# quadruped.net
KiCad netlist of a schematic drawn in Altium Designer
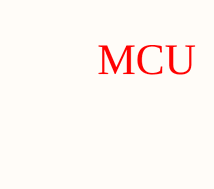
[diagram p0: quadruped.SchDoc, top left]
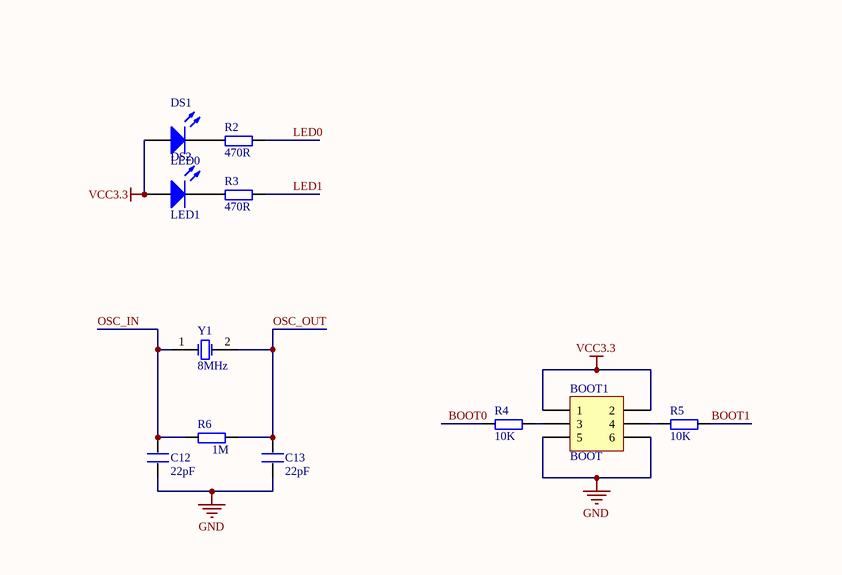
[diagram p1: quadruped.SchDoc, top right]
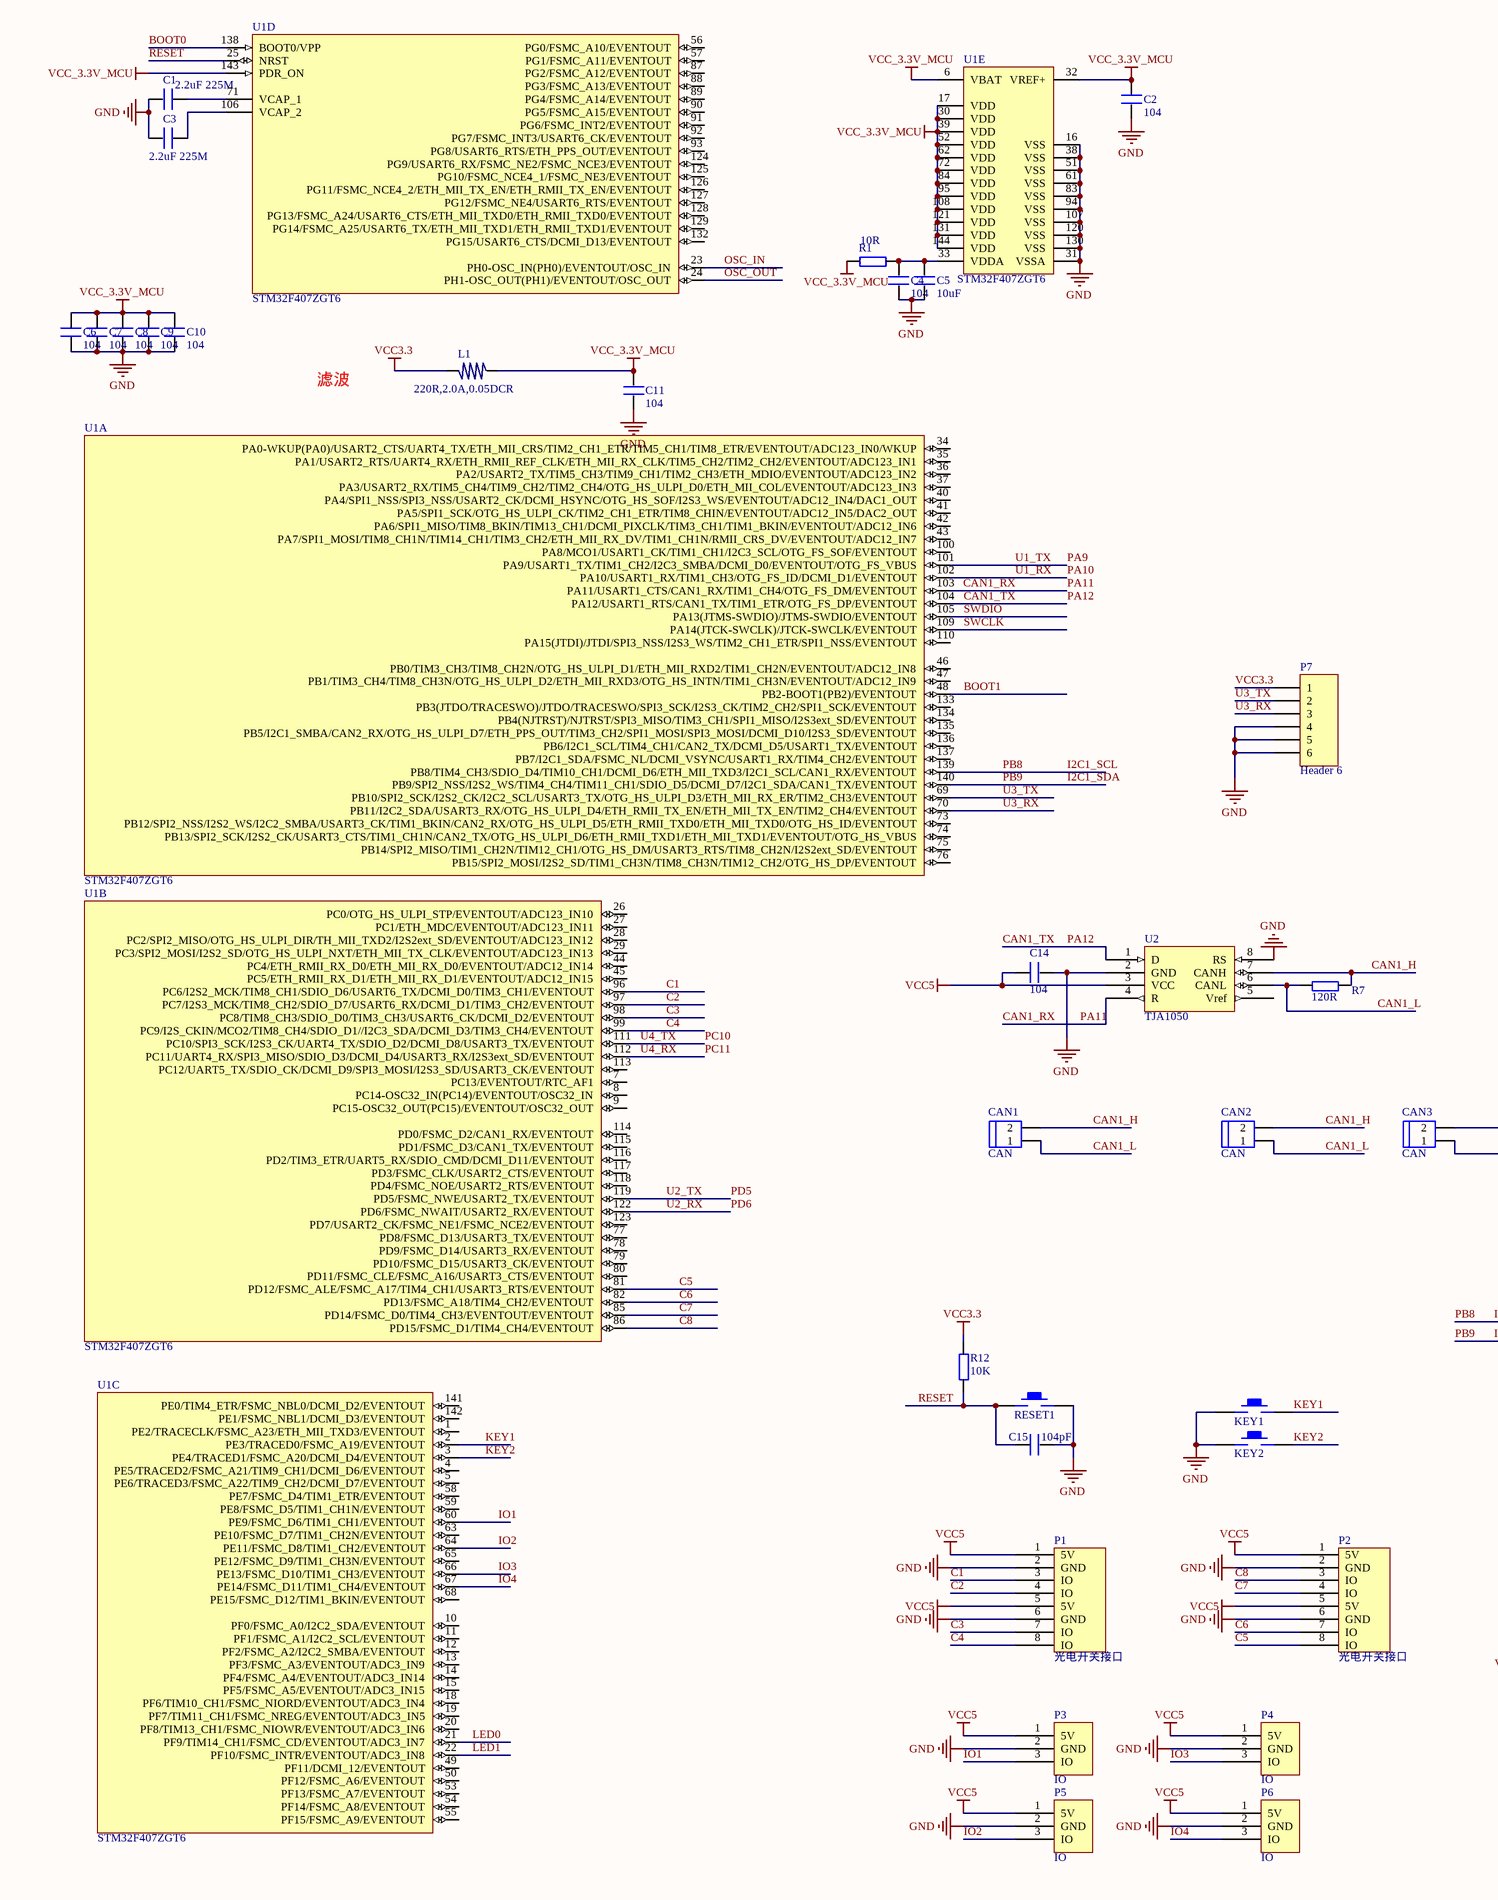
[diagram p2: quadruped.SchDoc, bottom left]
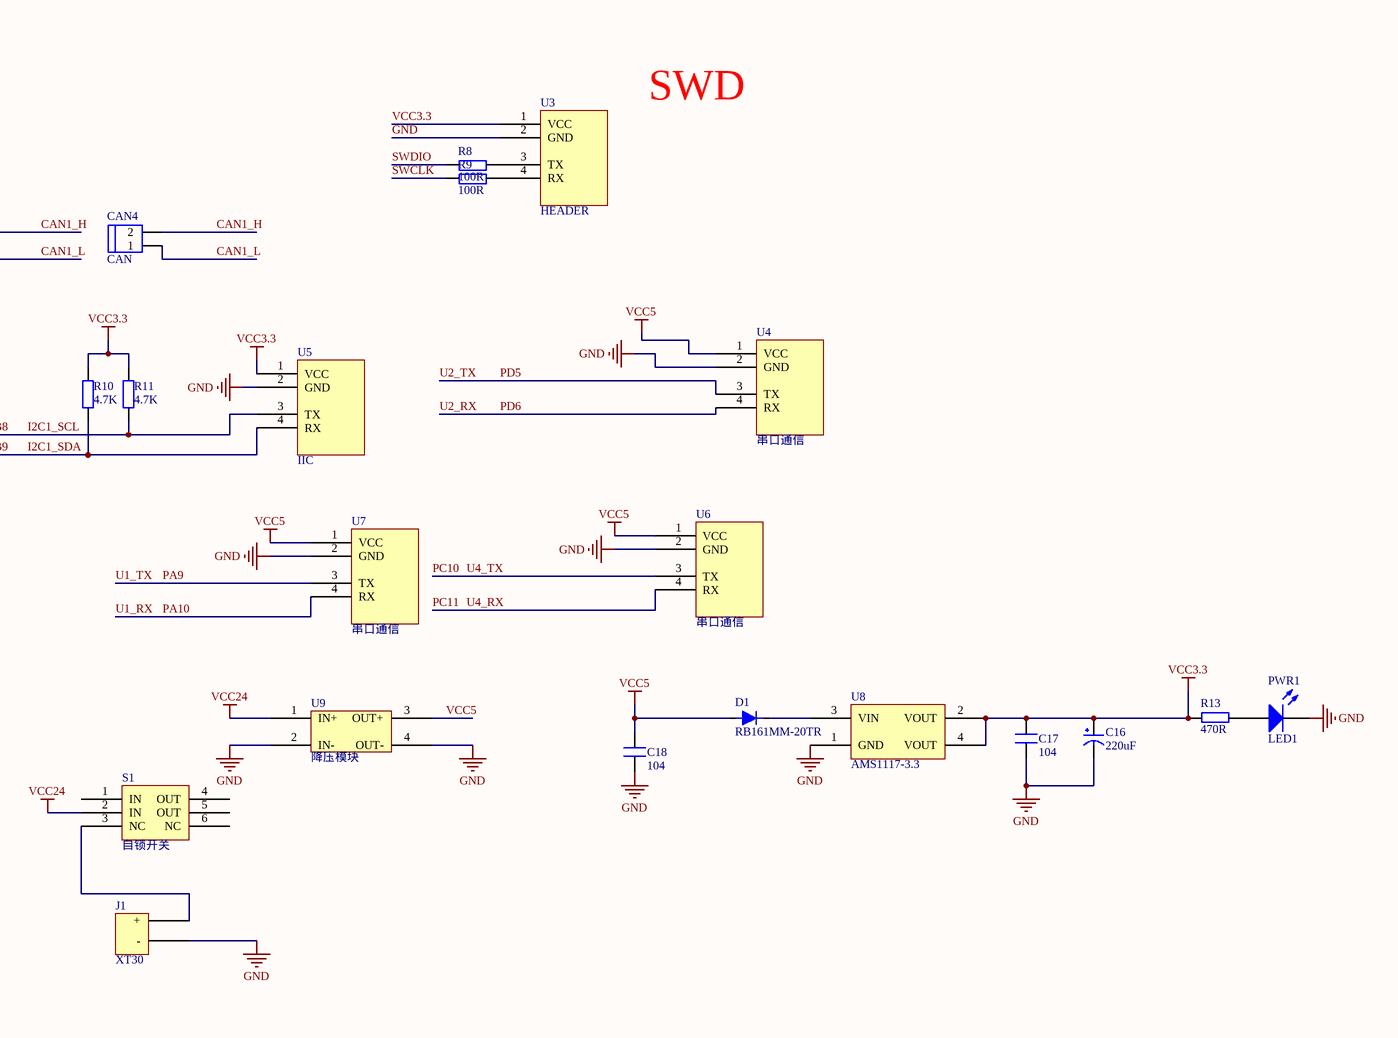
[diagram p3: quadruped.SchDoc, bottom right]

(export (version "E")
  (design (tool "Eeschema 10.0.6"))
  (components
    (comp (ref "BOOT1")
      (value "BOOT")
      (footprint "HDR2X3")
      (description "Header, 3-Pin, Dual row")
      (fields (field (name "PUBLISHER") "Altium Limited"))
      (libsource (lib "Explorer STM32F407封装库2") (part "Header 3X2"))
    )
    (comp (ref "C1")
      (value "2.2uF 225M")
      (footprint "0603C")
      (libsource (lib "Explorer STM32F407封装库") (part "C"))
    )
    (comp (ref "C2") (value "104") (footprint "0603C") (libsource (lib "Explorer STM32F407封装库") (part "C_1")))
    (comp (ref "C3")
      (value "2.2uF 225M")
      (footprint "0603C")
      (libsource (lib "Explorer STM32F407封装库") (part "C"))
    )
    (comp (ref "C4") (value "104") (footprint "0603C") (libsource (lib "Explorer STM32F407封装库") (part "C")))
    (comp (ref "C5") (value "10uF") (footprint "0603C") (libsource (lib "Explorer STM32F407封装库") (part "C")))
    (comp (ref "C6") (value "104") (footprint "0603C") (libsource (lib "Explorer STM32F407封装库") (part "C")))
    (comp (ref "C7") (value "104") (footprint "0603C") (libsource (lib "Explorer STM32F407封装库") (part "C")))
    (comp (ref "C8") (value "104") (footprint "0603C") (libsource (lib "Explorer STM32F407封装库") (part "C")))
    (comp (ref "C9") (value "104") (footprint "0603C") (libsource (lib "Explorer STM32F407封装库") (part "C")))
    (comp (ref "C10") (value "104") (footprint "0603C") (libsource (lib "Explorer STM32F407封装库") (part "C")))
    (comp (ref "C11") (value "104") (footprint "0603C") (libsource (lib "Explorer STM32F407封装库") (part "C")))
    (comp (ref "C12") (value "22pF") (footprint "0603C") (libsource (lib "Explorer STM32F407封装库") (part "C")))
    (comp (ref "C13") (value "22pF") (footprint "0603C") (libsource (lib "Explorer STM32F407封装库") (part "C")))
    (comp (ref "C14") (value "104") (footprint "0603C") (libsource (lib "Explorer STM32F407封装库") (part "C")))
    (comp (ref "C15")
      (value "104pF")
      (footprint "C0603")
      (libsource (lib "Explorer STM32F407封装库2") (part "C"))
    )
    (comp (ref "C16") (value "220uF") (footprint "C3528") (libsource (lib "EXPLORER") (part "CAP")))
    (comp (ref "C17")
      (value "104")
      (footprint "0603C")
      (libsource (lib "Explorer STM32F407封装库_SCH") (part "C"))
    )
    (comp (ref "C18")
      (value "104")
      (footprint "0603C")
      (libsource (lib "Explorer STM32F407封装库_SCH") (part "C"))
    )
    (comp (ref "CAN1")
      (value "CAN")
      (footprint "KF3.81直针-2P")
      (libsource (lib "Explorer STM32F407封装库") (part "HEAD2"))
    )
    (comp (ref "CAN2")
      (value "CAN")
      (footprint "KF3.81直针-2P")
      (libsource (lib "Explorer STM32F407封装库") (part "HEAD2"))
    )
    (comp (ref "CAN3")
      (value "CAN")
      (footprint "KF3.81直针-2P")
      (libsource (lib "Explorer STM32F407封装库") (part "HEAD2"))
    )
    (comp (ref "CAN4")
      (value "CAN")
      (footprint "KF3.81直针-2P")
      (libsource (lib "Explorer STM32F407封装库") (part "HEAD2"))
    )
    (comp (ref "D1") (value "RB161MM-20TR") (footprint "LC-SOD-123F") (libsource (lib "SCHlib") (part "肖特基")))
    (comp (ref "DS1")
      (value "LED0")
      (footprint "0603_LED")
      (description "Typical RED, GREEN, YELLOW, AMBER GaAs LED")
      (fields (field (name "PUBLISHER") "Altium Limited"))
      (libsource (lib "Explorer STM32F407封装库") (part "LED2"))
    )
    (comp (ref "DS2")
      (value "LED1")
      (footprint "0603_LED")
      (description "Typical RED, GREEN, YELLOW, AMBER GaAs LED")
      (fields (field (name "PUBLISHER") "Altium Limited"))
      (libsource (lib "Explorer STM32F407封装库") (part "LED2"))
    )
    (comp (ref "J1") (value "XT30") (footprint "POWER_PAD") (libsource (lib "MYSCHlib") (part "XT30")))
    (comp (ref "KEY1")
      (value "KEY0")
      (footprint "KEY_M")
      (libsource (lib "Explorer STM32F407封装库2") (part "KEY_M"))
    )
    (comp (ref "KEY2")
      (value "KEY0")
      (footprint "KEY_M")
      (libsource (lib "Explorer STM32F407封装库2") (part "KEY_M"))
    )
    (comp (ref "L1")
      (value "220R,2.0A,0.05DCR")
      (footprint "0603_L")
      (libsource (lib "Explorer STM32F407封装库") (part "L"))
    )
    (comp (ref "P1")
      (value "光电开关接口")
      (footprint "KF3.81直针-8P")
      (libsource (lib "MYSCHlib") (part "KF3.81-8P"))
    )
    (comp (ref "P2")
      (value "光电开关接口")
      (footprint "KF3.81直针-8P")
      (libsource (lib "MYSCHlib") (part "KF3.81-8P"))
    )
    (comp (ref "P3") (value "IO") (footprint "KF3.81直针-3P") (libsource (lib "MYSCHlib") (part "IO")))
    (comp (ref "P4") (value "IO") (footprint "KF3.81直针-3P") (libsource (lib "MYSCHlib") (part "IO")))
    (comp (ref "P5") (value "IO") (footprint "KF3.81直针-3P") (libsource (lib "MYSCHlib") (part "IO")))
    (comp (ref "P6") (value "IO") (footprint "KF3.81直针-3P") (libsource (lib "MYSCHlib") (part "IO")))
    (comp (ref "P7")
      (value "Header 6")
      (footprint "HDR1X6")
      (description "Header, 6-Pin")
      (fields (field (name "PUBLISHER") "Altium Limited"))
      (libsource (lib "Miscellaneous Connectors") (part "Header 6"))
    )
    (comp (ref "PWR1")
      (value "LED1")
      (footprint "0603_LED")
      (description "Typical RED, GREEN, YELLOW, AMBER GaAs LED")
      (fields (field (name "PUBLISHER") "Altium Limited"))
      (libsource (lib "Explorer STM32F407封装库") (part "LED2"))
    )
    (comp (ref "R1") (value "10R") (footprint "0603R") (libsource (lib "Explorer STM32F407封装库") (part "R")))
    (comp (ref "R2") (value "470R") (footprint "0603R") (libsource (lib "Explorer STM32F407封装库") (part "R")))
    (comp (ref "R3") (value "470R") (footprint "0603R") (libsource (lib "Explorer STM32F407封装库") (part "R")))
    (comp (ref "R4") (value "10K") (footprint "R0603") (libsource (lib "Explorer STM32F407封装库2") (part "R")))
    (comp (ref "R5") (value "10K") (footprint "R0603") (libsource (lib "Explorer STM32F407封装库2") (part "R")))
    (comp (ref "R6") (value "1M") (footprint "0603R") (libsource (lib "Explorer STM32F407封装库") (part "R")))
    (comp (ref "R7") (value "120R") (footprint "0603R") (libsource (lib "Explorer STM32F407封装库") (part "R")))
    (comp (ref "R8") (value "100R") (footprint "0603R") (libsource (lib "Explorer STM32F407封装库") (part "R")))
    (comp (ref "R9") (value "100R") (footprint "0603R") (libsource (lib "Explorer STM32F407封装库") (part "R")))
    (comp (ref "R10")
      (value "4.7K")
      (footprint "0603R")
      (description "R-0805")
      (libsource (lib "羽毛球团队") (part "R-0805"))
    )
    (comp (ref "R11")
      (value "4.7K")
      (footprint "0603R")
      (description "R-0805")
      (libsource (lib "羽毛球团队") (part "R-0805"))
    )
    (comp (ref "R12") (value "10K") (footprint "R0603") (libsource (lib "Explorer STM32F407封装库2") (part "R")))
    (comp (ref "R13")
      (value "470R")
      (footprint "0603R")
      (libsource (lib "Explorer STM32F407封装库_SCH") (part "R"))
    )
    (comp (ref "RESET1")
      (value "KEY_M")
      (footprint "KEY_4")
      (libsource (lib "Explorer STM32F407封装库2") (part "KEY_M"))
    )
    (comp (ref "S1")
      (value "自锁开关")
      (footprint "自锁开关5.8*5.8")
      (libsource (lib "MYSCHlib") (part "Switch_5.8"))
    )
    (comp (ref "U1")
      (value "STM32F407ZGT6")
      (footprint "lQFP144")
      (libsource (lib "Badminton封装库") (part "STM32F407ZGT6"))
    )
    (comp (ref "U2")
      (value "TJA1050")
      (footprint "SOP8")
      (libsource (lib "Explorer STM32F407封装库") (part "SN65HVD230D"))
    )
    (comp (ref "U3") (value "HEADER") (footprint "XH2.54-4") (libsource (lib "羽毛球团队") (part "XH2.54插座-4P")))
    (comp (ref "U4") (value "串口通信") (footprint "XH2.54-4") (libsource (lib "羽毛球团队") (part "XH2.54插座-4P")))
    (comp (ref "U5") (value "IIC") (footprint "XH2.54-4") (libsource (lib "羽毛球团队") (part "XH2.54插座-4P")))
    (comp (ref "U6") (value "串口通信") (footprint "XH2.54-4") (libsource (lib "羽毛球团队") (part "XH2.54插座-4P")))
    (comp (ref "U7") (value "串口通信") (footprint "XH2.54-4") (libsource (lib "羽毛球团队") (part "XH2.54插座-4P")))
    (comp (ref "U8") (value "AMS1117-3.3") (footprint "SOT223") (libsource (lib "74hc595") (part "AMS1117")))
    (comp (ref "U9")
      (value "降压模块")
      (footprint "MP1584N DC-DC")
      (libsource (lib "MYSCHlib") (part "MP1584N 降压模块"))
    )
    (comp (ref "Y1")
      (value "8MHz")
      (footprint "XTAL_US")
      (description "Crystal Oscillator")
      (fields (field (name "PUBLISHER") "Altium Limited"))
      (libsource (lib "EXPLORER_InitLib") (part "XTAL"))
    )
  )
  (nets
    (net (code "1") (name "/BOOT0") (class "Default")
      (node (ref "R4") (pin "1") (pintype "passive"))
      (node (ref "U1") (pin "138") (pinfunction "BOOT0/VPP_138") (pintype "input"))
    )
    (net (code "2") (name "/BOOT1") (class "Default")
      (node (ref "R5") (pin "2") (pintype "passive"))
      (node (ref "U1") (pin "48") (pinfunction "PB2-BOOT1(PB2)/EVENTOUT_48") (pintype "bidirectional"))
    )
    (net (code "3") (name "/C1") (class "Default")
      (node (ref "P1") (pin "3") (pinfunction "IO_3") (pintype "passive"))
      (node (ref "U1") (pin "96") (pinfunction "PC6/I2S2_MCK/TIM8_CH1/SDIO_D6/USART6_TX/DCMI_D0/TIM3_CH1/EVENTOUT_96") (pintype "bidirectional"))
    )
    (net (code "4") (name "/C2") (class "Default")
      (node (ref "P1") (pin "4") (pinfunction "IO_4") (pintype "passive"))
      (node (ref "U1") (pin "97") (pinfunction "PC7/I2S3_MCK/TIM8_CH2/SDIO_D7/USART6_RX/DCMI_D1/TIM3_CH2/EVENTOUT_97") (pintype "bidirectional"))
    )
    (net (code "5") (name "/C3") (class "Default")
      (node (ref "P1") (pin "7") (pinfunction "IO_7") (pintype "passive"))
      (node (ref "U1") (pin "98") (pinfunction "PC8/TIM8_CH3/SDIO_D0/TIM3_CH3/USART6_CK/DCMI_D2/EVENTOUT_98") (pintype "bidirectional"))
    )
    (net (code "6") (name "/C4") (class "Default")
      (node (ref "P1") (pin "8") (pinfunction "IO_8") (pintype "passive"))
      (node (ref "U1") (pin "99") (pinfunction "PC9/I2S_CKIN/MCO2/TIM8_CH4/SDIO_D1//I2C3_SDA/DCMI_D3/TIM3_CH4/EVENTOUT_99") (pintype "bidirectional"))
    )
    (net (code "7") (name "/C5") (class "Default")
      (node (ref "P2") (pin "8") (pinfunction "IO_8") (pintype "passive"))
      (node (ref "U1") (pin "81") (pinfunction "PD12/FSMC_ALE/FSMC_A17/TIM4_CH1/USART3_RTS/EVENTOUT_81") (pintype "bidirectional"))
    )
    (net (code "8") (name "/C6") (class "Default")
      (node (ref "P2") (pin "7") (pinfunction "IO_7") (pintype "passive"))
      (node (ref "U1") (pin "82") (pinfunction "PD13/FSMC_A18/TIM4_CH2/EVENTOUT_82") (pintype "bidirectional"))
    )
    (net (code "9") (name "/C7") (class "Default")
      (node (ref "P2") (pin "4") (pinfunction "IO_4") (pintype "passive"))
      (node (ref "U1") (pin "85") (pinfunction "PD14/FSMC_D0/TIM4_CH3/EVENTOUT/EVENTOUT_85") (pintype "bidirectional"))
    )
    (net (code "10") (name "/C8") (class "Default")
      (node (ref "P2") (pin "3") (pinfunction "IO_3") (pintype "passive"))
      (node (ref "U1") (pin "86") (pinfunction "PD15/FSMC_D1/TIM4_CH4/EVENTOUT_86") (pintype "bidirectional"))
    )
    (net (code "11") (name "/CAN1_H") (class "Default")
      (node (ref "CAN1") (pin "2") (pinfunction "2_2") (pintype "passive"))
      (node (ref "CAN2") (pin "2") (pinfunction "2_2") (pintype "passive"))
      (node (ref "CAN3") (pin "2") (pinfunction "2_2") (pintype "passive"))
      (node (ref "CAN4") (pin "2") (pinfunction "2_2") (pintype "passive"))
      (node (ref "R7") (pin "2") (pintype "passive"))
      (node (ref "U2") (pin "7") (pinfunction "CANH_7") (pintype "bidirectional"))
    )
    (net (code "12") (name "/CAN1_L") (class "Default")
      (node (ref "CAN1") (pin "1") (pinfunction "1_1") (pintype "passive"))
      (node (ref "CAN2") (pin "1") (pinfunction "1_1") (pintype "passive"))
      (node (ref "CAN3") (pin "1") (pinfunction "1_1") (pintype "passive"))
      (node (ref "CAN4") (pin "1") (pinfunction "1_1") (pintype "passive"))
      (node (ref "R7") (pin "1") (pintype "passive"))
      (node (ref "U2") (pin "6") (pinfunction "CANL_6") (pintype "bidirectional"))
    )
    (net (code "13") (name "/CAN1_RX") (class "Default")
      (node (ref "U1") (pin "103") (pinfunction "PA11/USART1_CTS/CAN1_RX/TIM1_CH4/OTG_FS_DM/EVENTOUT_103") (pintype "bidirectional"))
      (node (ref "U2") (pin "4") (pinfunction "R_4") (pintype "output"))
    )
    (net (code "14") (name "/CAN1_TX") (class "Default")
      (node (ref "U1") (pin "104") (pinfunction "PA12/USART1_RTS/CAN1_TX/TIM1_ETR/OTG_FS_DP/EVENTOUT_104") (pintype "bidirectional"))
      (node (ref "U2") (pin "1") (pinfunction "D_1") (pintype "input"))
    )
    (net (code "15") (name "/I2C1_SCL") (class "Default")
      (node (ref "R11") (pin "1") (pinfunction "1_1") (pintype "passive"))
      (node (ref "U1") (pin "139") (pinfunction "PB8/TIM4_CH3/SDIO_D4/TIM10_CH1/DCMI_D6/ETH_MII_TXD3/I2C1_SCL/CAN1_RX/EVENTOUT_139") (pintype "bidirectional"))
      (node (ref "U5") (pin "3") (pinfunction "TX_3") (pintype "passive"))
    )
    (net (code "16") (name "/I2C1_SDA") (class "Default")
      (node (ref "R10") (pin "1") (pinfunction "1_1") (pintype "passive"))
      (node (ref "U1") (pin "140") (pinfunction "PB9/SPI2_NSS/I2S2_WS/TIM4_CH4/TIM11_CH1/SDIO_D5/DCMI_D7/I2C1_SDA/CAN1_TX/EVENTOUT_140") (pintype "bidirectional"))
      (node (ref "U5") (pin "4") (pinfunction "RX_4") (pintype "passive"))
    )
    (net (code "17") (name "/IO1") (class "Default")
      (node (ref "P3") (pin "3") (pinfunction "IO_3") (pintype "passive"))
      (node (ref "U1") (pin "60") (pinfunction "PE9/FSMC_D6/TIM1_CH1/EVENTOUT_60") (pintype "bidirectional"))
    )
    (net (code "18") (name "/IO2") (class "Default")
      (node (ref "P5") (pin "3") (pinfunction "IO_3") (pintype "passive"))
      (node (ref "U1") (pin "64") (pinfunction "PE11/FSMC_D8/TIM1_CH2/EVENTOUT_64") (pintype "bidirectional"))
    )
    (net (code "19") (name "/IO3") (class "Default")
      (node (ref "P4") (pin "3") (pinfunction "IO_3") (pintype "passive"))
      (node (ref "U1") (pin "66") (pinfunction "PE13/FSMC_D10/TIM1_CH3/EVENTOUT_66") (pintype "bidirectional"))
    )
    (net (code "20") (name "/IO4") (class "Default")
      (node (ref "P6") (pin "3") (pinfunction "IO_3") (pintype "passive"))
      (node (ref "U1") (pin "67") (pinfunction "PE14/FSMC_D11/TIM1_CH4/EVENTOUT_67") (pintype "bidirectional"))
    )
    (net (code "21") (name "/KEY1") (class "Default")
      (node (ref "KEY1") (pin "2") (pinfunction "2_2") (pintype "passive"))
      (node (ref "U1") (pin "2") (pinfunction "PE3/TRACED0/FSMC_A19/EVENTOUT_2") (pintype "bidirectional"))
    )
    (net (code "22") (name "/KEY2") (class "Default")
      (node (ref "KEY2") (pin "2") (pinfunction "2_2") (pintype "passive"))
      (node (ref "U1") (pin "3") (pinfunction "PE4/TRACED1/FSMC_A20/DCMI_D4/EVENTOUT_3") (pintype "bidirectional"))
    )
    (net (code "23") (name "/LED0") (class "Default")
      (node (ref "R2") (pin "2") (pintype "passive"))
      (node (ref "U1") (pin "21") (pinfunction "PF9/TIM14_CH1/FSMC_CD/EVENTOUT/ADC3_IN7_21") (pintype "bidirectional"))
    )
    (net (code "24") (name "/LED1") (class "Default")
      (node (ref "R3") (pin "2") (pintype "passive"))
      (node (ref "U1") (pin "22") (pinfunction "PF10/FSMC_INTR/EVENTOUT/ADC3_IN8_22") (pintype "bidirectional"))
    )
    (net (code "25") (name "/OSC_IN") (class "Default")
      (node (ref "C12") (pin "2") (pintype "passive"))
      (node (ref "R6") (pin "1") (pintype "passive"))
      (node (ref "U1") (pin "23") (pinfunction "PH0-OSC_IN(PH0)/EVENTOUT/OSC_IN_23") (pintype "bidirectional"))
      (node (ref "Y1") (pin "1") (pinfunction "OSC1_1") (pintype "passive"))
    )
    (net (code "26") (name "/OSC_OUT") (class "Default")
      (node (ref "C13") (pin "2") (pintype "passive"))
      (node (ref "R6") (pin "2") (pintype "passive"))
      (node (ref "U1") (pin "24") (pinfunction "PH1-OSC_OUT(PH1)/EVENTOUT/OSC_OUT_24") (pintype "bidirectional"))
      (node (ref "Y1") (pin "2") (pinfunction "OSC2_2") (pintype "passive"))
    )
    (net (code "27") (name "/PA9") (class "Default")
      (node (ref "U1") (pin "101") (pinfunction "PA9/USART1_TX/TIM1_CH2/I2C3_SMBA/DCMI_D0/EVENTOUT/OTG_FS_VBUS_101") (pintype "bidirectional"))
      (node (ref "U7") (pin "3") (pinfunction "TX_3") (pintype "passive"))
    )
    (net (code "28") (name "/PA10") (class "Default")
      (node (ref "U1") (pin "102") (pinfunction "PA10/USART1_RX/TIM1_CH3/OTG_FS_ID/DCMI_D1/EVENTOUT_102") (pintype "bidirectional"))
      (node (ref "U7") (pin "4") (pinfunction "RX_4") (pintype "passive"))
    )
    (net (code "29") (name "/PC10") (class "Default")
      (node (ref "U1") (pin "111") (pinfunction "PC10/SPI3_SCK/I2S3_CK/UART4_TX/SDIO_D2/DCMI_D8/USART3_TX/EVENTOUT_111") (pintype "bidirectional"))
      (node (ref "U6") (pin "3") (pinfunction "TX_3") (pintype "passive"))
    )
    (net (code "30") (name "/PC11") (class "Default")
      (node (ref "U1") (pin "112") (pinfunction "PC11/UART4_RX/SPI3_MISO/SDIO_D3/DCMI_D4/USART3_RX/I2S3ext_SD/EVENTOUT_112") (pintype "bidirectional"))
      (node (ref "U6") (pin "4") (pinfunction "RX_4") (pintype "passive"))
    )
    (net (code "31") (name "/PD5") (class "Default")
      (node (ref "U1") (pin "119") (pinfunction "PD5/FSMC_NWE/USART2_TX/EVENTOUT_119") (pintype "bidirectional"))
      (node (ref "U4") (pin "3") (pinfunction "TX_3") (pintype "passive"))
    )
    (net (code "32") (name "/PD6") (class "Default")
      (node (ref "U1") (pin "122") (pinfunction "PD6/FSMC_NWAIT/USART2_RX/EVENTOUT_122") (pintype "bidirectional"))
      (node (ref "U4") (pin "4") (pinfunction "RX_4") (pintype "passive"))
    )
    (net (code "33") (name "/RESET") (class "Default")
      (node (ref "C15") (pin "2") (pintype "passive"))
      (node (ref "R12") (pin "1") (pintype "passive"))
      (node (ref "RESET1") (pin "1") (pinfunction "1_1") (pintype "passive"))
      (node (ref "U1") (pin "25") (pinfunction "NRST_25") (pintype "bidirectional"))
    )
    (net (code "34") (name "/SWCLK") (class "Default")
      (node (ref "R9") (pin "1") (pintype "passive"))
      (node (ref "U1") (pin "109") (pinfunction "PA14(JTCK-SWCLK)/JTCK-SWCLK/EVENTOUT_109") (pintype "bidirectional"))
    )
    (net (code "35") (name "/SWDIO") (class "Default")
      (node (ref "R8") (pin "1") (pintype "passive"))
      (node (ref "U1") (pin "105") (pinfunction "PA13(JTMS-SWDIO)/JTMS-SWDIO/EVENTOUT_105") (pintype "bidirectional"))
    )
    (net (code "36") (name "/U3_RX") (class "Default")
      (node (ref "P7") (pin "3") (pinfunction "3_3") (pintype "passive"))
      (node (ref "U1") (pin "70") (pinfunction "PB11/I2C2_SDA/USART3_RX/OTG_HS_ULPI_D4/ETH_RMII_TX_EN/ETH_MII_TX_EN/TIM2_CH4/EVENTOUT_70") (pintype "bidirectional"))
    )
    (net (code "37") (name "/U3_TX") (class "Default")
      (node (ref "P7") (pin "2") (pinfunction "2_2") (pintype "passive"))
      (node (ref "U1") (pin "69") (pinfunction "PB10/SPI2_SCK/I2S2_CK/I2C2_SCL/USART3_TX/OTG_HS_ULPI_D3/ETH_MII_RX_ER/TIM2_CH3/EVENTOUT_69") (pintype "bidirectional"))
    )
    (net (code "38") (name "GND") (class "Default")
      (node (ref "BOOT1") (pin "5") (pinfunction "5_5") (pintype "passive"))
      (node (ref "BOOT1") (pin "6") (pinfunction "6_6") (pintype "passive"))
      (node (ref "C1") (pin "1") (pintype "passive"))
      (node (ref "C10") (pin "1") (pintype "passive"))
      (node (ref "C11") (pin "1") (pintype "passive"))
      (node (ref "C12") (pin "1") (pintype "passive"))
      (node (ref "C13") (pin "1") (pintype "passive"))
      (node (ref "C14") (pin "2") (pintype "passive"))
      (node (ref "C15") (pin "1") (pintype "passive"))
      (node (ref "C16") (pin "2") (pinfunction "GND_2") (pintype "passive"))
      (node (ref "C17") (pin "1") (pintype "passive"))
      (node (ref "C18") (pin "1") (pintype "passive"))
      (node (ref "C2") (pin "1") (pintype "passive"))
      (node (ref "C3") (pin "2") (pintype "passive"))
      (node (ref "C4") (pin "1") (pintype "passive"))
      (node (ref "C5") (pin "1") (pintype "passive"))
      (node (ref "C6") (pin "1") (pintype "passive"))
      (node (ref "C7") (pin "1") (pintype "passive"))
      (node (ref "C8") (pin "1") (pintype "passive"))
      (node (ref "C9") (pin "1") (pintype "passive"))
      (node (ref "J1") (pin "0") (pinfunction "-_0") (pintype "passive"))
      (node (ref "KEY1") (pin "1") (pinfunction "1_1") (pintype "passive"))
      (node (ref "KEY2") (pin "1") (pinfunction "1_1") (pintype "passive"))
      (node (ref "P1") (pin "2") (pinfunction "GND_2") (pintype "passive"))
      (node (ref "P1") (pin "6") (pinfunction "GND_6") (pintype "passive"))
      (node (ref "P2") (pin "2") (pinfunction "GND_2") (pintype "passive"))
      (node (ref "P2") (pin "6") (pinfunction "GND_6") (pintype "passive"))
      (node (ref "P3") (pin "2") (pinfunction "GND_2") (pintype "passive"))
      (node (ref "P4") (pin "2") (pinfunction "GND_2") (pintype "passive"))
      (node (ref "P5") (pin "2") (pinfunction "GND_2") (pintype "passive"))
      (node (ref "P6") (pin "2") (pinfunction "GND_2") (pintype "passive"))
      (node (ref "P7") (pin "4") (pinfunction "4_4") (pintype "passive"))
      (node (ref "P7") (pin "5") (pinfunction "5_5") (pintype "passive"))
      (node (ref "P7") (pin "6") (pinfunction "6_6") (pintype "passive"))
      (node (ref "PWR1") (pin "2") (pinfunction "K_2") (pintype "passive"))
      (node (ref "RESET1") (pin "2") (pinfunction "2_2") (pintype "passive"))
      (node (ref "U1") (pin "107") (pinfunction "VSS_107") (pintype "power_in"))
      (node (ref "U1") (pin "120") (pinfunction "VSS_120") (pintype "power_in"))
      (node (ref "U1") (pin "130") (pinfunction "VSS_130") (pintype "power_in"))
      (node (ref "U1") (pin "16") (pinfunction "VSS_16") (pintype "power_in"))
      (node (ref "U1") (pin "31") (pinfunction "VSSA_31") (pintype "power_in"))
      (node (ref "U1") (pin "38") (pinfunction "VSS_38") (pintype "power_in"))
      (node (ref "U1") (pin "51") (pinfunction "VSS_51") (pintype "power_in"))
      (node (ref "U1") (pin "61") (pinfunction "VSS_61") (pintype "power_in"))
      (node (ref "U1") (pin "83") (pinfunction "VSS_83") (pintype "power_in"))
      (node (ref "U1") (pin "94") (pinfunction "VSS_94") (pintype "power_in"))
      (node (ref "U2") (pin "2") (pinfunction "GND_2") (pintype "power_in"))
      (node (ref "U2") (pin "8") (pinfunction "RS_8") (pintype "input"))
      (node (ref "U3") (pin "2") (pinfunction "GND_2") (pintype "passive"))
      (node (ref "U4") (pin "2") (pinfunction "GND_2") (pintype "passive"))
      (node (ref "U5") (pin "2") (pinfunction "GND_2") (pintype "passive"))
      (node (ref "U6") (pin "2") (pinfunction "GND_2") (pintype "passive"))
      (node (ref "U7") (pin "2") (pinfunction "GND_2") (pintype "passive"))
      (node (ref "U8") (pin "1") (pinfunction "GND_1") (pintype "passive"))
      (node (ref "U9") (pin "2") (pinfunction "IN-_2") (pintype "passive"))
      (node (ref "U9") (pin "4") (pinfunction "OUT-_4") (pintype "passive"))
    )
    (net (code "39") (name "Net-(BOOT1-Pad3)") (class "Default")
      (node (ref "BOOT1") (pin "3") (pinfunction "3_3") (pintype "passive"))
      (node (ref "R4") (pin "2") (pintype "passive"))
    )
    (net (code "40") (name "Net-(BOOT1-Pad4)") (class "Default")
      (node (ref "BOOT1") (pin "4") (pinfunction "4_4") (pintype "passive"))
      (node (ref "R5") (pin "1") (pintype "passive"))
    )
    (net (code "41") (name "Net-(DS1-K)") (class "Default")
      (node (ref "DS1") (pin "2") (pinfunction "K_2") (pintype "passive"))
      (node (ref "R2") (pin "1") (pintype "passive"))
    )
    (net (code "42") (name "Net-(DS2-K)") (class "Default")
      (node (ref "DS2") (pin "2") (pinfunction "K_2") (pintype "passive"))
      (node (ref "R3") (pin "1") (pintype "passive"))
    )
    (net (code "43") (name "Net-(J1-+)") (class "Default")
      (node (ref "J1") (pin "1") (pinfunction "+_1") (pintype "passive"))
      (node (ref "S1") (pin "3") (pinfunction "NC_3") (pintype "passive"))
    )
    (net (code "44") (name "Net-(PWR1-A)") (class "Default")
      (node (ref "PWR1") (pin "1") (pinfunction "A_1") (pintype "passive"))
      (node (ref "R13") (pin "1") (pintype "passive"))
    )
    (net (code "45") (name "Net-(U1D-VCAP_1)") (class "Default")
      (node (ref "C1") (pin "2") (pintype "passive"))
      (node (ref "U1") (pin "71") (pinfunction "VCAP_1_71") (pintype "power_in"))
    )
    (net (code "46") (name "Net-(U1D-VCAP_2)") (class "Default")
      (node (ref "C3") (pin "1") (pintype "passive"))
      (node (ref "U1") (pin "106") (pinfunction "VCAP_2_106") (pintype "power_in"))
    )
    (net (code "47") (name "Net-(U1E-VDDA)") (class "Default")
      (node (ref "C4") (pin "2") (pintype "passive"))
      (node (ref "C5") (pin "2") (pintype "passive"))
      (node (ref "R1") (pin "2") (pintype "passive"))
      (node (ref "U1") (pin "33") (pinfunction "VDDA_33") (pintype "power_in"))
    )
    (net (code "48") (name "Net-(U3-RX)") (class "Default")
      (node (ref "R9") (pin "2") (pintype "passive"))
      (node (ref "U3") (pin "4") (pinfunction "RX_4") (pintype "passive"))
    )
    (net (code "49") (name "Net-(U3-TX)") (class "Default")
      (node (ref "R8") (pin "2") (pintype "passive"))
      (node (ref "U3") (pin "3") (pinfunction "TX_3") (pintype "passive"))
    )
    (net (code "50") (name "Net-(U8-VIN)") (class "Default")
      (node (ref "D1") (pin "2") (pinfunction "2_2") (pintype "passive"))
      (node (ref "U8") (pin "3") (pinfunction "VIN_3") (pintype "passive"))
    )
    (net (code "51") (name "VCC3.3") (class "Default")
      (node (ref "BOOT1") (pin "1") (pinfunction "1_1") (pintype "passive"))
      (node (ref "BOOT1") (pin "2") (pinfunction "2_2") (pintype "passive"))
      (node (ref "C16") (pin "1") (pinfunction "VCC_1") (pintype "passive"))
      (node (ref "C17") (pin "2") (pintype "passive"))
      (node (ref "DS1") (pin "1") (pinfunction "A_1") (pintype "passive"))
      (node (ref "DS2") (pin "1") (pinfunction "A_1") (pintype "passive"))
      (node (ref "L1") (pin "2") (pintype "passive"))
      (node (ref "P7") (pin "1") (pinfunction "1_1") (pintype "passive"))
      (node (ref "R10") (pin "2") (pinfunction "2_2") (pintype "passive"))
      (node (ref "R11") (pin "2") (pinfunction "2_2") (pintype "passive"))
      (node (ref "R12") (pin "2") (pintype "passive"))
      (node (ref "R13") (pin "2") (pintype "passive"))
      (node (ref "U3") (pin "1") (pinfunction "VCC_1") (pintype "passive"))
      (node (ref "U5") (pin "1") (pinfunction "VCC_1") (pintype "passive"))
      (node (ref "U8") (pin "2") (pinfunction "VOUT_2") (pintype "passive"))
      (node (ref "U8") (pin "4") (pinfunction "VOUT_4") (pintype "passive"))
    )
    (net (code "52") (name "VCC5") (class "Default")
      (node (ref "C14") (pin "1") (pintype "passive"))
      (node (ref "C18") (pin "2") (pintype "passive"))
      (node (ref "D1") (pin "1") (pinfunction "1_1") (pintype "passive"))
      (node (ref "P1") (pin "1") (pinfunction "5V_1") (pintype "passive"))
      (node (ref "P1") (pin "5") (pinfunction "5V_5") (pintype "passive"))
      (node (ref "P2") (pin "1") (pinfunction "5V_1") (pintype "passive"))
      (node (ref "P2") (pin "5") (pinfunction "5V_5") (pintype "passive"))
      (node (ref "P3") (pin "1") (pinfunction "5V_1") (pintype "passive"))
      (node (ref "P4") (pin "1") (pinfunction "5V_1") (pintype "passive"))
      (node (ref "P5") (pin "1") (pinfunction "5V_1") (pintype "passive"))
      (node (ref "P6") (pin "1") (pinfunction "5V_1") (pintype "passive"))
      (node (ref "U2") (pin "3") (pinfunction "VCC_3") (pintype "power_in"))
      (node (ref "U4") (pin "1") (pinfunction "VCC_1") (pintype "passive"))
      (node (ref "U6") (pin "1") (pinfunction "VCC_1") (pintype "passive"))
      (node (ref "U7") (pin "1") (pinfunction "VCC_1") (pintype "passive"))
      (node (ref "U9") (pin "3") (pinfunction "OUT+_3") (pintype "passive"))
    )
    (net (code "53") (name "VCC24") (class "Default")
      (node (ref "S1") (pin "2") (pinfunction "IN_2") (pintype "passive"))
      (node (ref "U9") (pin "1") (pinfunction "IN+_1") (pintype "passive"))
    )
    (net (code "54") (name "VCC_3.3V_MCU") (class "Default")
      (node (ref "C10") (pin "2") (pintype "passive"))
      (node (ref "C11") (pin "2") (pintype "passive"))
      (node (ref "C2") (pin "2") (pintype "passive"))
      (node (ref "C6") (pin "2") (pintype "passive"))
      (node (ref "C7") (pin "2") (pintype "passive"))
      (node (ref "C8") (pin "2") (pintype "passive"))
      (node (ref "C9") (pin "2") (pintype "passive"))
      (node (ref "L1") (pin "1") (pintype "passive"))
      (node (ref "R1") (pin "1") (pintype "passive"))
      (node (ref "U1") (pin "108") (pinfunction "VDD_108") (pintype "power_in"))
      (node (ref "U1") (pin "121") (pinfunction "VDD_121") (pintype "power_in"))
      (node (ref "U1") (pin "131") (pinfunction "VDD_131") (pintype "power_in"))
      (node (ref "U1") (pin "143") (pinfunction "PDR_ON_143") (pintype "input"))
      (node (ref "U1") (pin "144") (pinfunction "VDD_144") (pintype "power_in"))
      (node (ref "U1") (pin "17") (pinfunction "VDD_17") (pintype "power_in"))
      (node (ref "U1") (pin "30") (pinfunction "VDD_30") (pintype "power_in"))
      (node (ref "U1") (pin "32") (pinfunction "VREF+_32") (pintype "power_in"))
      (node (ref "U1") (pin "39") (pinfunction "VDD_39") (pintype "power_in"))
      (node (ref "U1") (pin "52") (pinfunction "VDD_52") (pintype "power_in"))
      (node (ref "U1") (pin "6") (pinfunction "VBAT_6") (pintype "power_in"))
      (node (ref "U1") (pin "62") (pinfunction "VDD_62") (pintype "power_in"))
      (node (ref "U1") (pin "72") (pinfunction "VDD_72") (pintype "power_in"))
      (node (ref "U1") (pin "84") (pinfunction "VDD_84") (pintype "power_in"))
      (node (ref "U1") (pin "95") (pinfunction "VDD_95") (pintype "power_in"))
    )
    (net (code "55") (name "unconnected-(S1-IN-Pad1)") (class "Default")
      (node (ref "S1") (pin "1") (pinfunction "IN_1") (pintype "passive"))
    )
    (net (code "56") (name "unconnected-(S1-NC-Pad6)") (class "Default")
      (node (ref "S1") (pin "6") (pinfunction "NC_6") (pintype "passive"))
    )
    (net (code "57") (name "unconnected-(S1-OUT-Pad4)") (class "Default")
      (node (ref "S1") (pin "4") (pinfunction "OUT_4") (pintype "passive"))
    )
    (net (code "58") (name "unconnected-(S1-OUT-Pad5)") (class "Default")
      (node (ref "S1") (pin "5") (pinfunction "OUT_5") (pintype "passive"))
    )
    (net (code "59") (name "unconnected-(U1A-PA0-WKUP(PA0){slash}USART2_CTS{slash}UART4_TX{slash}ETH_MII_CRS{slash}TIM2_CH1_ETR{slash}TIM5_CH1{slash}TIM8_ETR{slash}EVENTOUT{slash}ADC123_IN0{slash}WKUP-Pad34)") (class "Default")
      (node (ref "U1") (pin "34") (pinfunction "PA0-WKUP(PA0)/USART2_CTS/UART4_TX/ETH_MII_CRS/TIM2_CH1_ETR/TIM5_CH1/TIM8_ETR/EVENTOUT/ADC123_IN0/WKUP_34") (pintype "bidirectional"))
    )
    (net (code "60") (name "unconnected-(U1A-PA1{slash}USART2_RTS{slash}UART4_RX{slash}ETH_RMII_REF_CLK{slash}ETH_MII_RX_CLK{slash}TIM5_CH2{slash}TIM2_CH2{slash}EVENTOUT{slash}ADC123_IN1-Pad35)") (class "Default")
      (node (ref "U1") (pin "35") (pinfunction "PA1/USART2_RTS/UART4_RX/ETH_RMII_REF_CLK/ETH_MII_RX_CLK/TIM5_CH2/TIM2_CH2/EVENTOUT/ADC123_IN1_35") (pintype "bidirectional"))
    )
    (net (code "61") (name "unconnected-(U1A-PA2{slash}USART2_TX{slash}TIM5_CH3{slash}TIM9_CH1{slash}TIM2_CH3{slash}ETH_MDIO{slash}EVENTOUT{slash}ADC123_IN2-Pad36)") (class "Default")
      (node (ref "U1") (pin "36") (pinfunction "PA2/USART2_TX/TIM5_CH3/TIM9_CH1/TIM2_CH3/ETH_MDIO/EVENTOUT/ADC123_IN2_36") (pintype "bidirectional"))
    )
    (net (code "62") (name "unconnected-(U1A-PA3{slash}USART2_RX{slash}TIM5_CH4{slash}TIM9_CH2{slash}TIM2_CH4{slash}OTG_HS_ULPI_D0{slash}ETH_MII_COL{slash}EVENTOUT{slash}ADC123_IN3-Pad37)") (class "Default")
      (node (ref "U1") (pin "37") (pinfunction "PA3/USART2_RX/TIM5_CH4/TIM9_CH2/TIM2_CH4/OTG_HS_ULPI_D0/ETH_MII_COL/EVENTOUT/ADC123_IN3_37") (pintype "bidirectional"))
    )
    (net (code "63") (name "unconnected-(U1A-PA4{slash}SPI1_NSS{slash}SPI3_NSS{slash}USART2_CK{slash}DCMI_HSYNC{slash}OTG_HS_SOF{slash}I2S3_WS{slash}EVENTOUT{slash}ADC12_IN4{slash}DAC1_OUT-Pad40)") (class "Default")
      (node (ref "U1") (pin "40") (pinfunction "PA4/SPI1_NSS/SPI3_NSS/USART2_CK/DCMI_HSYNC/OTG_HS_SOF/I2S3_WS/EVENTOUT/ADC12_IN4/DAC1_OUT_40") (pintype "bidirectional"))
    )
    (net (code "64") (name "unconnected-(U1A-PA5{slash}SPI1_SCK{slash}OTG_HS_ULPI_CK{slash}TIM2_CH1_ETR{slash}TIM8_CHIN{slash}EVENTOUT{slash}ADC12_IN5{slash}DAC2_OUT-Pad41)") (class "Default")
      (node (ref "U1") (pin "41") (pinfunction "PA5/SPI1_SCK/OTG_HS_ULPI_CK/TIM2_CH1_ETR/TIM8_CHIN/EVENTOUT/ADC12_IN5/DAC2_OUT_41") (pintype "bidirectional"))
    )
    (net (code "65") (name "unconnected-(U1A-PA6{slash}SPI1_MISO{slash}TIM8_BKIN{slash}TIM13_CH1{slash}DCMI_PIXCLK{slash}TIM3_CH1{slash}TIM1_BKIN{slash}EVENTOUT{slash}ADC12_IN6-Pad42)") (class "Default")
      (node (ref "U1") (pin "42") (pinfunction "PA6/SPI1_MISO/TIM8_BKIN/TIM13_CH1/DCMI_PIXCLK/TIM3_CH1/TIM1_BKIN/EVENTOUT/ADC12_IN6_42") (pintype "bidirectional"))
    )
    (net (code "66") (name "unconnected-(U1A-PA7{slash}SPI1_MOSI{slash}TIM8_CH1N{slash}TIM14_CH1{slash}TIM3_CH2{slash}ETH_MII_RX_DV{slash}TIM1_CH1N{slash}RMII_CRS_DV{slash}EVENTOUT{slash}ADC12_IN7-Pad43)") (class "Default")
      (node (ref "U1") (pin "43") (pinfunction "PA7/SPI1_MOSI/TIM8_CH1N/TIM14_CH1/TIM3_CH2/ETH_MII_RX_DV/TIM1_CH1N/RMII_CRS_DV/EVENTOUT/ADC12_IN7_43") (pintype "bidirectional"))
    )
    (net (code "67") (name "unconnected-(U1A-PA8{slash}MCO1{slash}USART1_CK{slash}TIM1_CH1{slash}I2C3_SCL{slash}OTG_FS_SOF{slash}EVENTOUT-Pad100)") (class "Default")
      (node (ref "U1") (pin "100") (pinfunction "PA8/MCO1/USART1_CK/TIM1_CH1/I2C3_SCL/OTG_FS_SOF/EVENTOUT_100") (pintype "bidirectional"))
    )
    (net (code "68") (name "unconnected-(U1A-PA15(JTDI){slash}JTDI{slash}SPI3_NSS{slash}I2S3_WS{slash}TIM2_CH1_ETR{slash}SPI1_NSS{slash}EVENTOUT-Pad110)") (class "Default")
      (node (ref "U1") (pin "110") (pinfunction "PA15(JTDI)/JTDI/SPI3_NSS/I2S3_WS/TIM2_CH1_ETR/SPI1_NSS/EVENTOUT_110") (pintype "bidirectional"))
    )
    (net (code "69") (name "unconnected-(U1A-PB0{slash}TIM3_CH3{slash}TIM8_CH2N{slash}OTG_HS_ULPI_D1{slash}ETH_MII_RXD2{slash}TIM1_CH2N{slash}EVENTOUT{slash}ADC12_IN8-Pad46)") (class "Default")
      (node (ref "U1") (pin "46") (pinfunction "PB0/TIM3_CH3/TIM8_CH2N/OTG_HS_ULPI_D1/ETH_MII_RXD2/TIM1_CH2N/EVENTOUT/ADC12_IN8_46") (pintype "bidirectional"))
    )
    (net (code "70") (name "unconnected-(U1A-PB1{slash}TIM3_CH4{slash}TIM8_CH3N{slash}OTG_HS_ULPI_D2{slash}ETH_MII_RXD3{slash}OTG_HS_INTN{slash}TIM1_CH3N{slash}EVENTOUT{slash}ADC12_IN9-Pad47)") (class "Default")
      (node (ref "U1") (pin "47") (pinfunction "PB1/TIM3_CH4/TIM8_CH3N/OTG_HS_ULPI_D2/ETH_MII_RXD3/OTG_HS_INTN/TIM1_CH3N/EVENTOUT/ADC12_IN9_47") (pintype "bidirectional"))
    )
    (net (code "71") (name "unconnected-(U1A-PB3(JTDO{slash}TRACESWO){slash}JTDO{slash}TRACESWO{slash}SPI3_SCK{slash}I2S3_CK{slash}TIM2_CH2{slash}SPI1_SCK{slash}EVENTOUT-Pad133)") (class "Default")
      (node (ref "U1") (pin "133") (pinfunction "PB3(JTDO/TRACESWO)/JTDO/TRACESWO/SPI3_SCK/I2S3_CK/TIM2_CH2/SPI1_SCK/EVENTOUT_133") (pintype "bidirectional"))
    )
    (net (code "72") (name "unconnected-(U1A-PB4(NJTRST){slash}NJTRST{slash}SPI3_MISO{slash}TIM3_CH1{slash}SPI1_MISO{slash}I2S3ext_SD{slash}EVENTOUT-Pad134)") (class "Default")
      (node (ref "U1") (pin "134") (pinfunction "PB4(NJTRST)/NJTRST/SPI3_MISO/TIM3_CH1/SPI1_MISO/I2S3ext_SD/EVENTOUT_134") (pintype "bidirectional"))
    )
    (net (code "73") (name "unconnected-(U1A-PB5{slash}I2C1_SMBA{slash}CAN2_RX{slash}OTG_HS_ULPI_D7{slash}ETH_PPS_OUT{slash}TIM3_CH2{slash}SPI1_MOSI{slash}SPI3_MOSI{slash}DCMI_D10{slash}I2S3_SD{slash}EVENTOUT-Pad135)") (class "Default")
      (node (ref "U1") (pin "135") (pinfunction "PB5/I2C1_SMBA/CAN2_RX/OTG_HS_ULPI_D7/ETH_PPS_OUT/TIM3_CH2/SPI1_MOSI/SPI3_MOSI/DCMI_D10/I2S3_SD/EVENTOUT_135") (pintype "bidirectional"))
    )
    (net (code "74") (name "unconnected-(U1A-PB6{slash}I2C1_SCL{slash}TIM4_CH1{slash}CAN2_TX{slash}DCMI_D5{slash}USART1_TX{slash}EVENTOUT-Pad136)") (class "Default")
      (node (ref "U1") (pin "136") (pinfunction "PB6/I2C1_SCL/TIM4_CH1/CAN2_TX/DCMI_D5/USART1_TX/EVENTOUT_136") (pintype "bidirectional"))
    )
    (net (code "75") (name "unconnected-(U1A-PB7{slash}I2C1_SDA{slash}FSMC_NL{slash}DCMI_VSYNC{slash}USART1_RX{slash}TIM4_CH2{slash}EVENTOUT-Pad137)") (class "Default")
      (node (ref "U1") (pin "137") (pinfunction "PB7/I2C1_SDA/FSMC_NL/DCMI_VSYNC/USART1_RX/TIM4_CH2/EVENTOUT_137") (pintype "bidirectional"))
    )
    (net (code "76") (name "unconnected-(U1A-PB12{slash}SPI2_NSS{slash}I2S2_WS{slash}I2C2_SMBA{slash}USART3_CK{slash}TIM1_BKIN{slash}CAN2_RX{slash}OTG_HS_ULPI_D5{slash}ETH_RMII_TXD0{slash}ETH_MII_TXD0{slash}OTG_HS_ID{slash}EVENTOUT-Pad73)") (class "Default")
      (node (ref "U1") (pin "73") (pinfunction "PB12/SPI2_NSS/I2S2_WS/I2C2_SMBA/USART3_CK/TIM1_BKIN/CAN2_RX/OTG_HS_ULPI_D5/ETH_RMII_TXD0/ETH_MII_TXD0/OTG_HS_ID/EVENTOUT_73") (pintype "bidirectional"))
    )
    (net (code "77") (name "unconnected-(U1A-PB13{slash}SPI2_SCK{slash}I2S2_CK{slash}USART3_CTS{slash}TIM1_CH1N{slash}CAN2_TX{slash}OTG_HS_ULPI_D6{slash}ETH_RMII_TXD1{slash}ETH_MII_TXD1{slash}EVENTOUT{slash}OTG_HS_VBUS-Pad74)") (class "Default")
      (node (ref "U1") (pin "74") (pinfunction "PB13/SPI2_SCK/I2S2_CK/USART3_CTS/TIM1_CH1N/CAN2_TX/OTG_HS_ULPI_D6/ETH_RMII_TXD1/ETH_MII_TXD1/EVENTOUT/OTG_HS_VBUS_74") (pintype "bidirectional"))
    )
    (net (code "78") (name "unconnected-(U1A-PB14{slash}SPI2_MISO{slash}TIM1_CH2N{slash}TIM12_CH1{slash}OTG_HS_DM{slash}USART3_RTS{slash}TIM8_CH2N{slash}I2S2ext_SD{slash}EVENTOUT-Pad75)") (class "Default")
      (node (ref "U1") (pin "75") (pinfunction "PB14/SPI2_MISO/TIM1_CH2N/TIM12_CH1/OTG_HS_DM/USART3_RTS/TIM8_CH2N/I2S2ext_SD/EVENTOUT_75") (pintype "bidirectional"))
    )
    (net (code "79") (name "unconnected-(U1A-PB15{slash}SPI2_MOSI{slash}I2S2_SD{slash}TIM1_CH3N{slash}TIM8_CH3N{slash}TIM12_CH2{slash}OTG_HS_DP{slash}EVENTOUT-Pad76)") (class "Default")
      (node (ref "U1") (pin "76") (pinfunction "PB15/SPI2_MOSI/I2S2_SD/TIM1_CH3N/TIM8_CH3N/TIM12_CH2/OTG_HS_DP/EVENTOUT_76") (pintype "bidirectional"))
    )
    (net (code "80") (name "unconnected-(U1B-PC0{slash}OTG_HS_ULPI_STP{slash}EVENTOUT{slash}ADC123_IN10-Pad26)") (class "Default")
      (node (ref "U1") (pin "26") (pinfunction "PC0/OTG_HS_ULPI_STP/EVENTOUT/ADC123_IN10_26") (pintype "bidirectional"))
    )
    (net (code "81") (name "unconnected-(U1B-PC1{slash}ETH_MDC{slash}EVENTOUT{slash}ADC123_IN11-Pad27)") (class "Default")
      (node (ref "U1") (pin "27") (pinfunction "PC1/ETH_MDC/EVENTOUT/ADC123_IN11_27") (pintype "bidirectional"))
    )
    (net (code "82") (name "unconnected-(U1B-PC2{slash}SPI2_MISO{slash}OTG_HS_ULPI_DIR{slash}TH_MII_TXD2{slash}I2S2ext_SD{slash}EVENTOUT{slash}ADC123_IN12-Pad28)") (class "Default")
      (node (ref "U1") (pin "28") (pinfunction "PC2/SPI2_MISO/OTG_HS_ULPI_DIR/TH_MII_TXD2/I2S2ext_SD/EVENTOUT/ADC123_IN12_28") (pintype "bidirectional"))
    )
    (net (code "83") (name "unconnected-(U1B-PC3{slash}SPI2_MOSI{slash}I2S2_SD{slash}OTG_HS_ULPI_NXT{slash}ETH_MII_TX_CLK{slash}EVENTOUT{slash}ADC123_IN13-Pad29)") (class "Default")
      (node (ref "U1") (pin "29") (pinfunction "PC3/SPI2_MOSI/I2S2_SD/OTG_HS_ULPI_NXT/ETH_MII_TX_CLK/EVENTOUT/ADC123_IN13_29") (pintype "bidirectional"))
    )
    (net (code "84") (name "unconnected-(U1B-PC4{slash}ETH_RMII_RX_D0{slash}ETH_MII_RX_D0{slash}EVENTOUT{slash}ADC12_IN14-Pad44)") (class "Default")
      (node (ref "U1") (pin "44") (pinfunction "PC4/ETH_RMII_RX_D0/ETH_MII_RX_D0/EVENTOUT/ADC12_IN14_44") (pintype "bidirectional"))
    )
    (net (code "85") (name "unconnected-(U1B-PC5{slash}ETH_RMII_RX_D1{slash}ETH_MII_RX_D1{slash}EVENTOUT{slash}ADC12_IN15-Pad45)") (class "Default")
      (node (ref "U1") (pin "45") (pinfunction "PC5/ETH_RMII_RX_D1/ETH_MII_RX_D1/EVENTOUT/ADC12_IN15_45") (pintype "bidirectional"))
    )
    (net (code "86") (name "unconnected-(U1B-PC12{slash}UART5_TX{slash}SDIO_CK{slash}DCMI_D9{slash}SPI3_MOSI{slash}I2S3_SD{slash}USART3_CK{slash}EVENTOUT-Pad113)") (class "Default")
      (node (ref "U1") (pin "113") (pinfunction "PC12/UART5_TX/SDIO_CK/DCMI_D9/SPI3_MOSI/I2S3_SD/USART3_CK/EVENTOUT_113") (pintype "bidirectional"))
    )
    (net (code "87") (name "unconnected-(U1B-PC13{slash}EVENTOUT{slash}RTC_AF1-Pad7)") (class "Default")
      (node (ref "U1") (pin "7") (pinfunction "PC13/EVENTOUT/RTC_AF1_7") (pintype "bidirectional"))
    )
    (net (code "88") (name "unconnected-(U1B-PC14-OSC32_IN(PC14){slash}EVENTOUT{slash}OSC32_IN-Pad8)") (class "Default")
      (node (ref "U1") (pin "8") (pinfunction "PC14-OSC32_IN(PC14)/EVENTOUT/OSC32_IN_8") (pintype "bidirectional"))
    )
    (net (code "89") (name "unconnected-(U1B-PC15-OSC32_OUT(PC15){slash}EVENTOUT{slash}OSC32_OUT-Pad9)") (class "Default")
      (node (ref "U1") (pin "9") (pinfunction "PC15-OSC32_OUT(PC15)/EVENTOUT/OSC32_OUT_9") (pintype "bidirectional"))
    )
    (net (code "90") (name "unconnected-(U1B-PD0{slash}FSMC_D2{slash}CAN1_RX{slash}EVENTOUT-Pad114)") (class "Default")
      (node (ref "U1") (pin "114") (pinfunction "PD0/FSMC_D2/CAN1_RX/EVENTOUT_114") (pintype "bidirectional"))
    )
    (net (code "91") (name "unconnected-(U1B-PD1{slash}FSMC_D3{slash}CAN1_TX{slash}EVENTOUT-Pad115)") (class "Default")
      (node (ref "U1") (pin "115") (pinfunction "PD1/FSMC_D3/CAN1_TX/EVENTOUT_115") (pintype "bidirectional"))
    )
    (net (code "92") (name "unconnected-(U1B-PD2{slash}TIM3_ETR{slash}UART5_RX{slash}SDIO_CMD{slash}DCMI_D11{slash}EVENTOUT-Pad116)") (class "Default")
      (node (ref "U1") (pin "116") (pinfunction "PD2/TIM3_ETR/UART5_RX/SDIO_CMD/DCMI_D11/EVENTOUT_116") (pintype "bidirectional"))
    )
    (net (code "93") (name "unconnected-(U1B-PD3{slash}FSMC_CLK{slash}USART2_CTS{slash}EVENTOUT-Pad117)") (class "Default")
      (node (ref "U1") (pin "117") (pinfunction "PD3/FSMC_CLK/USART2_CTS/EVENTOUT_117") (pintype "bidirectional"))
    )
    (net (code "94") (name "unconnected-(U1B-PD4{slash}FSMC_NOE{slash}USART2_RTS{slash}EVENTOUT-Pad118)") (class "Default")
      (node (ref "U1") (pin "118") (pinfunction "PD4/FSMC_NOE/USART2_RTS/EVENTOUT_118") (pintype "bidirectional"))
    )
    (net (code "95") (name "unconnected-(U1B-PD7{slash}USART2_CK{slash}FSMC_NE1{slash}FSMC_NCE2{slash}EVENTOUT-Pad123)") (class "Default")
      (node (ref "U1") (pin "123") (pinfunction "PD7/USART2_CK/FSMC_NE1/FSMC_NCE2/EVENTOUT_123") (pintype "bidirectional"))
    )
    (net (code "96") (name "unconnected-(U1B-PD8{slash}FSMC_D13{slash}USART3_TX{slash}EVENTOUT-Pad77)") (class "Default")
      (node (ref "U1") (pin "77") (pinfunction "PD8/FSMC_D13/USART3_TX/EVENTOUT_77") (pintype "bidirectional"))
    )
    (net (code "97") (name "unconnected-(U1B-PD9{slash}FSMC_D14{slash}USART3_RX{slash}EVENTOUT-Pad78)") (class "Default")
      (node (ref "U1") (pin "78") (pinfunction "PD9/FSMC_D14/USART3_RX/EVENTOUT_78") (pintype "bidirectional"))
    )
    (net (code "98") (name "unconnected-(U1B-PD10{slash}FSMC_D15{slash}USART3_CK{slash}EVENTOUT-Pad79)") (class "Default")
      (node (ref "U1") (pin "79") (pinfunction "PD10/FSMC_D15/USART3_CK/EVENTOUT_79") (pintype "bidirectional"))
    )
    (net (code "99") (name "unconnected-(U1B-PD11{slash}FSMC_CLE{slash}FSMC_A16{slash}USART3_CTS{slash}EVENTOUT-Pad80)") (class "Default")
      (node (ref "U1") (pin "80") (pinfunction "PD11/FSMC_CLE/FSMC_A16/USART3_CTS/EVENTOUT_80") (pintype "bidirectional"))
    )
    (net (code "100") (name "unconnected-(U1C-PE0{slash}TIM4_ETR{slash}FSMC_NBL0{slash}DCMI_D2{slash}EVENTOUT-Pad141)") (class "Default")
      (node (ref "U1") (pin "141") (pinfunction "PE0/TIM4_ETR/FSMC_NBL0/DCMI_D2/EVENTOUT_141") (pintype "bidirectional"))
    )
    (net (code "101") (name "unconnected-(U1C-PE1{slash}FSMC_NBL1{slash}DCMI_D3{slash}EVENTOUT-Pad142)") (class "Default")
      (node (ref "U1") (pin "142") (pinfunction "PE1/FSMC_NBL1/DCMI_D3/EVENTOUT_142") (pintype "bidirectional"))
    )
    (net (code "102") (name "unconnected-(U1C-PE2{slash}TRACECLK{slash}FSMC_A23{slash}ETH_MII_TXD3{slash}EVENTOUT-Pad1)") (class "Default")
      (node (ref "U1") (pin "1") (pinfunction "PE2/TRACECLK/FSMC_A23/ETH_MII_TXD3/EVENTOUT_1") (pintype "bidirectional"))
    )
    (net (code "103") (name "unconnected-(U1C-PE5{slash}TRACED2{slash}FSMC_A21{slash}TIM9_CH1{slash}DCMI_D6{slash}EVENTOUT-Pad4)") (class "Default")
      (node (ref "U1") (pin "4") (pinfunction "PE5/TRACED2/FSMC_A21/TIM9_CH1/DCMI_D6/EVENTOUT_4") (pintype "bidirectional"))
    )
    (net (code "104") (name "unconnected-(U1C-PE6{slash}TRACED3{slash}FSMC_A22{slash}TIM9_CH2{slash}DCMI_D7{slash}EVENTOUT-Pad5)") (class "Default")
      (node (ref "U1") (pin "5") (pinfunction "PE6/TRACED3/FSMC_A22/TIM9_CH2/DCMI_D7/EVENTOUT_5") (pintype "bidirectional"))
    )
    (net (code "105") (name "unconnected-(U1C-PE7{slash}FSMC_D4{slash}TIM1_ETR{slash}EVENTOUT-Pad58)") (class "Default")
      (node (ref "U1") (pin "58") (pinfunction "PE7/FSMC_D4/TIM1_ETR/EVENTOUT_58") (pintype "bidirectional"))
    )
    (net (code "106") (name "unconnected-(U1C-PE8{slash}FSMC_D5{slash}TIM1_CH1N{slash}EVENTOUT-Pad59)") (class "Default")
      (node (ref "U1") (pin "59") (pinfunction "PE8/FSMC_D5/TIM1_CH1N/EVENTOUT_59") (pintype "bidirectional"))
    )
    (net (code "107") (name "unconnected-(U1C-PE10{slash}FSMC_D7{slash}TIM1_CH2N{slash}EVENTOUT-Pad63)") (class "Default")
      (node (ref "U1") (pin "63") (pinfunction "PE10/FSMC_D7/TIM1_CH2N/EVENTOUT_63") (pintype "bidirectional"))
    )
    (net (code "108") (name "unconnected-(U1C-PE12{slash}FSMC_D9{slash}TIM1_CH3N{slash}EVENTOUT-Pad65)") (class "Default")
      (node (ref "U1") (pin "65") (pinfunction "PE12/FSMC_D9/TIM1_CH3N/EVENTOUT_65") (pintype "bidirectional"))
    )
    (net (code "109") (name "unconnected-(U1C-PE15{slash}FSMC_D12{slash}TIM1_BKIN{slash}EVENTOUT-Pad68)") (class "Default")
      (node (ref "U1") (pin "68") (pinfunction "PE15/FSMC_D12/TIM1_BKIN/EVENTOUT_68") (pintype "bidirectional"))
    )
    (net (code "110") (name "unconnected-(U1C-PF0{slash}FSMC_A0{slash}I2C2_SDA{slash}EVENTOUT-Pad10)") (class "Default")
      (node (ref "U1") (pin "10") (pinfunction "PF0/FSMC_A0/I2C2_SDA/EVENTOUT_10") (pintype "bidirectional"))
    )
    (net (code "111") (name "unconnected-(U1C-PF1{slash}FSMC_A1{slash}I2C2_SCL{slash}EVENTOUT-Pad11)") (class "Default")
      (node (ref "U1") (pin "11") (pinfunction "PF1/FSMC_A1/I2C2_SCL/EVENTOUT_11") (pintype "bidirectional"))
    )
    (net (code "112") (name "unconnected-(U1C-PF2{slash}FSMC_A2{slash}I2C2_SMBA{slash}EVENTOUT-Pad12)") (class "Default")
      (node (ref "U1") (pin "12") (pinfunction "PF2/FSMC_A2/I2C2_SMBA/EVENTOUT_12") (pintype "bidirectional"))
    )
    (net (code "113") (name "unconnected-(U1C-PF3{slash}FSMC_A3{slash}EVENTOUT{slash}ADC3_IN9-Pad13)") (class "Default")
      (node (ref "U1") (pin "13") (pinfunction "PF3/FSMC_A3/EVENTOUT/ADC3_IN9_13") (pintype "bidirectional"))
    )
    (net (code "114") (name "unconnected-(U1C-PF4{slash}FSMC_A4{slash}EVENTOUT{slash}ADC3_IN14-Pad14)") (class "Default")
      (node (ref "U1") (pin "14") (pinfunction "PF4/FSMC_A4/EVENTOUT/ADC3_IN14_14") (pintype "bidirectional"))
    )
    (net (code "115") (name "unconnected-(U1C-PF5{slash}FSMC_A5{slash}EVENTOUT{slash}ADC3_IN15-Pad15)") (class "Default")
      (node (ref "U1") (pin "15") (pinfunction "PF5/FSMC_A5/EVENTOUT/ADC3_IN15_15") (pintype "bidirectional"))
    )
    (net (code "116") (name "unconnected-(U1C-PF6{slash}TIM10_CH1{slash}FSMC_NIORD{slash}EVENTOUT{slash}ADC3_IN4-Pad18)") (class "Default")
      (node (ref "U1") (pin "18") (pinfunction "PF6/TIM10_CH1/FSMC_NIORD/EVENTOUT/ADC3_IN4_18") (pintype "bidirectional"))
    )
    (net (code "117") (name "unconnected-(U1C-PF7{slash}TIM11_CH1{slash}FSMC_NREG{slash}EVENTOUT{slash}ADC3_IN5-Pad19)") (class "Default")
      (node (ref "U1") (pin "19") (pinfunction "PF7/TIM11_CH1/FSMC_NREG/EVENTOUT/ADC3_IN5_19") (pintype "bidirectional"))
    )
    (net (code "118") (name "unconnected-(U1C-PF8{slash}TIM13_CH1{slash}FSMC_NIOWR{slash}EVENTOUT{slash}ADC3_IN6-Pad20)") (class "Default")
      (node (ref "U1") (pin "20") (pinfunction "PF8/TIM13_CH1/FSMC_NIOWR/EVENTOUT/ADC3_IN6_20") (pintype "bidirectional"))
    )
    (net (code "119") (name "unconnected-(U1C-PF11{slash}DCMI_12{slash}EVENTOUT-Pad49)") (class "Default")
      (node (ref "U1") (pin "49") (pinfunction "PF11/DCMI_12/EVENTOUT_49") (pintype "bidirectional"))
    )
    (net (code "120") (name "unconnected-(U1C-PF12{slash}FSMC_A6{slash}EVENTOUT-Pad50)") (class "Default")
      (node (ref "U1") (pin "50") (pinfunction "PF12/FSMC_A6/EVENTOUT_50") (pintype "bidirectional"))
    )
    (net (code "121") (name "unconnected-(U1C-PF13{slash}FSMC_A7{slash}EVENTOUT-Pad53)") (class "Default")
      (node (ref "U1") (pin "53") (pinfunction "PF13/FSMC_A7/EVENTOUT_53") (pintype "bidirectional"))
    )
    (net (code "122") (name "unconnected-(U1C-PF14{slash}FSMC_A8{slash}EVENTOUT-Pad54)") (class "Default")
      (node (ref "U1") (pin "54") (pinfunction "PF14/FSMC_A8/EVENTOUT_54") (pintype "bidirectional"))
    )
    (net (code "123") (name "unconnected-(U1C-PF15{slash}FSMC_A9{slash}EVENTOUT-Pad55)") (class "Default")
      (node (ref "U1") (pin "55") (pinfunction "PF15/FSMC_A9/EVENTOUT_55") (pintype "bidirectional"))
    )
    (net (code "124") (name "unconnected-(U1D-PG0{slash}FSMC_A10{slash}EVENTOUT-Pad56)") (class "Default")
      (node (ref "U1") (pin "56") (pinfunction "PG0/FSMC_A10/EVENTOUT_56") (pintype "bidirectional"))
    )
    (net (code "125") (name "unconnected-(U1D-PG1{slash}FSMC_A11{slash}EVENTOUT-Pad57)") (class "Default")
      (node (ref "U1") (pin "57") (pinfunction "PG1/FSMC_A11/EVENTOUT_57") (pintype "bidirectional"))
    )
    (net (code "126") (name "unconnected-(U1D-PG2{slash}FSMC_A12{slash}EVENTOUT-Pad87)") (class "Default")
      (node (ref "U1") (pin "87") (pinfunction "PG2/FSMC_A12/EVENTOUT_87") (pintype "bidirectional"))
    )
    (net (code "127") (name "unconnected-(U1D-PG3{slash}FSMC_A13{slash}EVENTOUT-Pad88)") (class "Default")
      (node (ref "U1") (pin "88") (pinfunction "PG3/FSMC_A13/EVENTOUT_88") (pintype "bidirectional"))
    )
    (net (code "128") (name "unconnected-(U1D-PG4{slash}FSMC_A14{slash}EVENTOUT-Pad89)") (class "Default")
      (node (ref "U1") (pin "89") (pinfunction "PG4/FSMC_A14/EVENTOUT_89") (pintype "bidirectional"))
    )
    (net (code "129") (name "unconnected-(U1D-PG5{slash}FSMC_A15{slash}EVENTOUT-Pad90)") (class "Default")
      (node (ref "U1") (pin "90") (pinfunction "PG5/FSMC_A15/EVENTOUT_90") (pintype "bidirectional"))
    )
    (net (code "130") (name "unconnected-(U1D-PG6{slash}FSMC_INT2{slash}EVENTOUT-Pad91)") (class "Default")
      (node (ref "U1") (pin "91") (pinfunction "PG6/FSMC_INT2/EVENTOUT_91") (pintype "bidirectional"))
    )
    (net (code "131") (name "unconnected-(U1D-PG7{slash}FSMC_INT3{slash}USART6_CK{slash}EVENTOUT-Pad92)") (class "Default")
      (node (ref "U1") (pin "92") (pinfunction "PG7/FSMC_INT3/USART6_CK/EVENTOUT_92") (pintype "bidirectional"))
    )
    (net (code "132") (name "unconnected-(U1D-PG8{slash}USART6_RTS{slash}ETH_PPS_OUT{slash}EVENTOUT-Pad93)") (class "Default")
      (node (ref "U1") (pin "93") (pinfunction "PG8/USART6_RTS/ETH_PPS_OUT/EVENTOUT_93") (pintype "bidirectional"))
    )
    (net (code "133") (name "unconnected-(U1D-PG9{slash}USART6_RX{slash}FSMC_NE2{slash}FSMC_NCE3{slash}EVENTOUT-Pad124)") (class "Default")
      (node (ref "U1") (pin "124") (pinfunction "PG9/USART6_RX/FSMC_NE2/FSMC_NCE3/EVENTOUT_124") (pintype "bidirectional"))
    )
    (net (code "134") (name "unconnected-(U1D-PG10{slash}FSMC_NCE4_1{slash}FSMC_NE3{slash}EVENTOUT-Pad125)") (class "Default")
      (node (ref "U1") (pin "125") (pinfunction "PG10/FSMC_NCE4_1/FSMC_NE3/EVENTOUT_125") (pintype "bidirectional"))
    )
    (net (code "135") (name "unconnected-(U1D-PG11{slash}FSMC_NCE4_2{slash}ETH_MII_TX_EN{slash}ETH_RMII_TX_EN{slash}EVENTOUT-Pad126)") (class "Default")
      (node (ref "U1") (pin "126") (pinfunction "PG11/FSMC_NCE4_2/ETH_MII_TX_EN/ETH_RMII_TX_EN/EVENTOUT_126") (pintype "bidirectional"))
    )
    (net (code "136") (name "unconnected-(U1D-PG12{slash}FSMC_NE4{slash}USART6_RTS{slash}EVENTOUT-Pad127)") (class "Default")
      (node (ref "U1") (pin "127") (pinfunction "PG12/FSMC_NE4/USART6_RTS/EVENTOUT_127") (pintype "bidirectional"))
    )
    (net (code "137") (name "unconnected-(U1D-PG13{slash}FSMC_A24{slash}USART6_CTS{slash}ETH_MII_TXD0{slash}ETH_RMII_TXD0{slash}EVENTOUT-Pad128)") (class "Default")
      (node (ref "U1") (pin "128") (pinfunction "PG13/FSMC_A24/USART6_CTS/ETH_MII_TXD0/ETH_RMII_TXD0/EVENTOUT_128") (pintype "bidirectional"))
    )
    (net (code "138") (name "unconnected-(U1D-PG14{slash}FSMC_A25{slash}USART6_TX{slash}ETH_MII_TXD1{slash}ETH_RMII_TXD1{slash}EVENTOUT-Pad129)") (class "Default")
      (node (ref "U1") (pin "129") (pinfunction "PG14/FSMC_A25/USART6_TX/ETH_MII_TXD1/ETH_RMII_TXD1/EVENTOUT_129") (pintype "bidirectional"))
    )
    (net (code "139") (name "unconnected-(U1D-PG15{slash}USART6_CTS{slash}DCMI_D13{slash}EVENTOUT-Pad132)") (class "Default")
      (node (ref "U1") (pin "132") (pinfunction "PG15/USART6_CTS/DCMI_D13/EVENTOUT_132") (pintype "bidirectional"))
    )
    (net (code "140") (name "unconnected-(U2-Vref-Pad5)") (class "Default")
      (node (ref "U2") (pin "5") (pinfunction "Vref_5") (pintype "output"))
    )
  )
)
